# ledcube.net
KiCad netlist of a schematic drawn in EAGLE
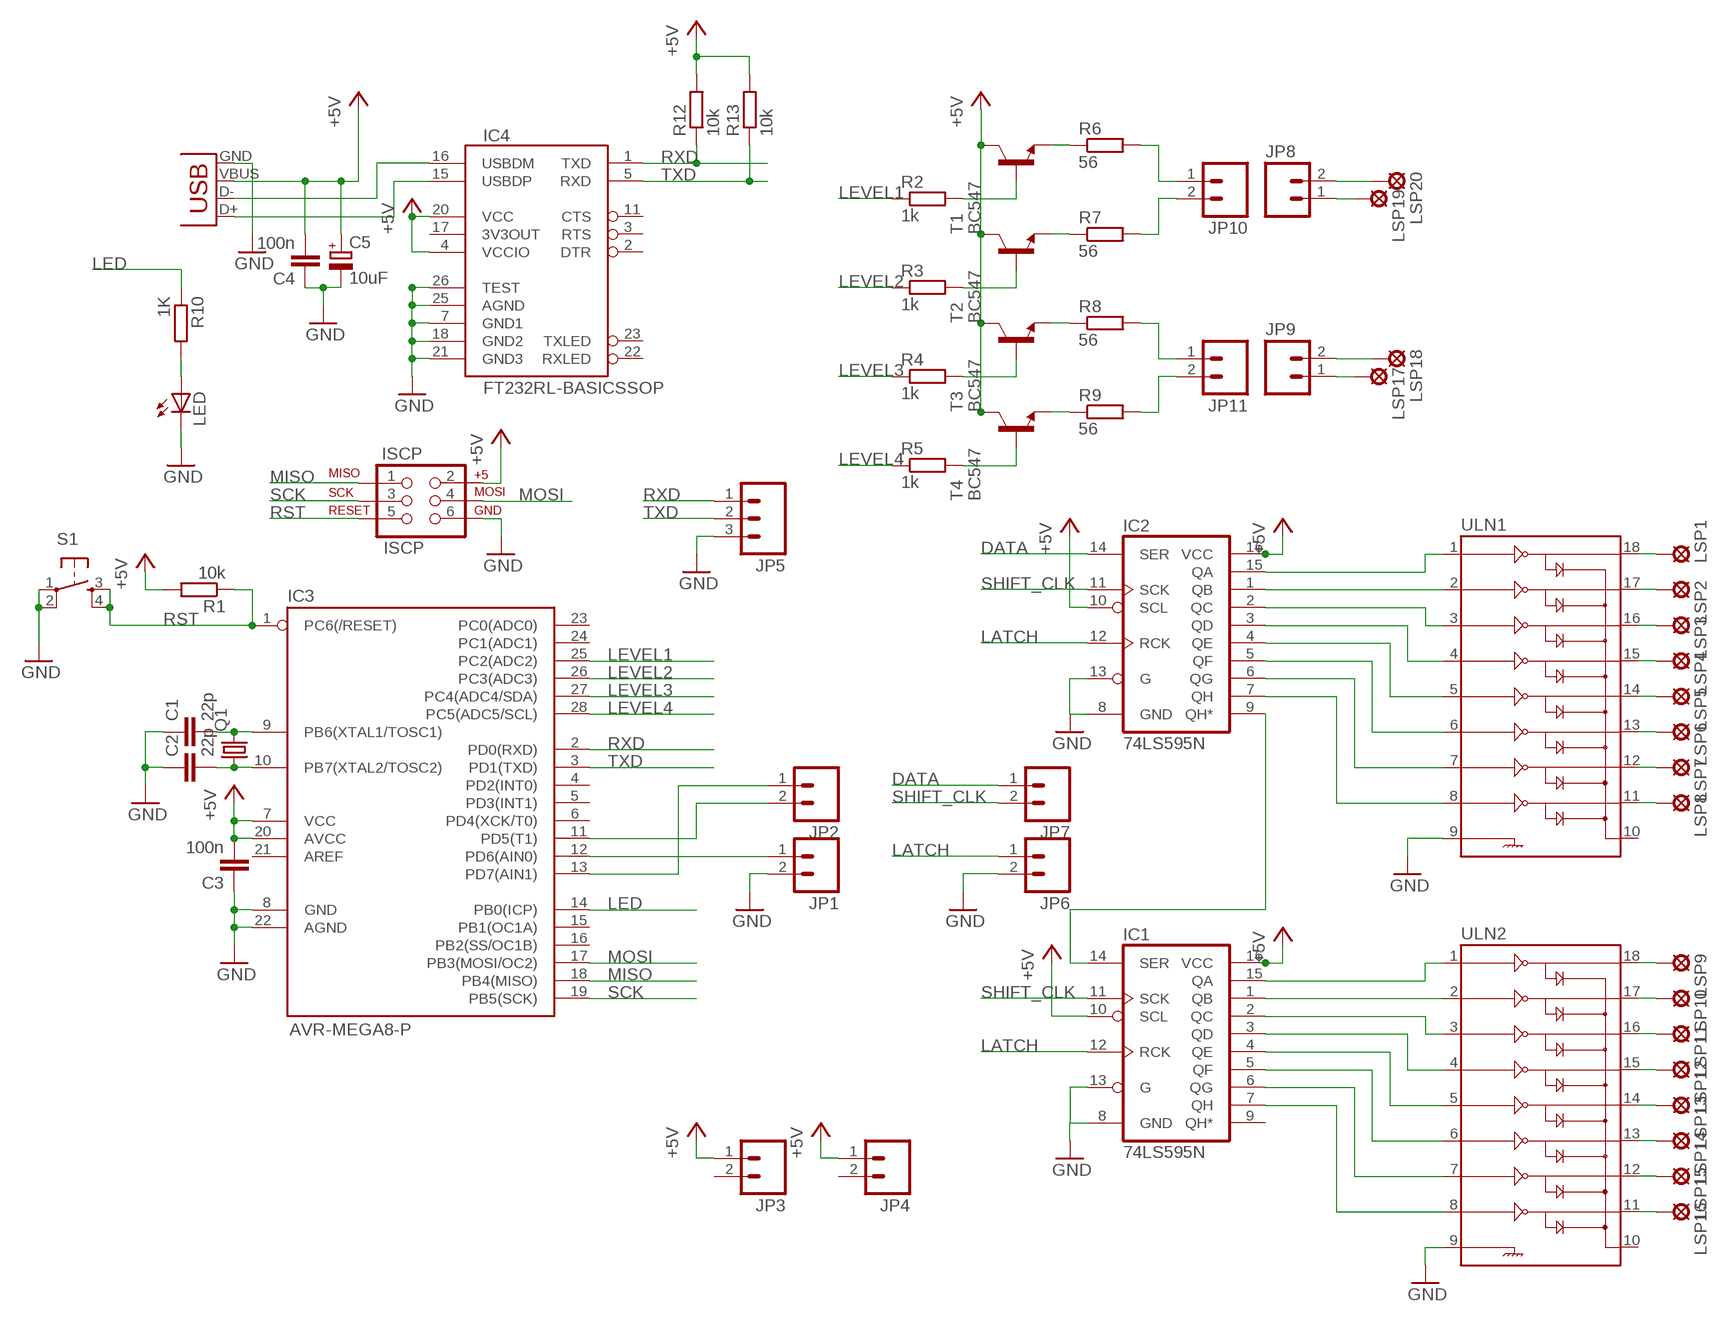
[diagram p0: schematic, sheet 1]

(export (version "E")
  (design (tool "Eeschema 10.0.6"))
  (components
    (comp (ref "C1")
      (value "22p")
      (footprint "eagle-import:C050-024X044")
      (libsource (lib "eagle-import") (part "C-EU050-024X044"))
    )
    (comp (ref "C2")
      (value "22p")
      (footprint "eagle-import:C050-024X044")
      (libsource (lib "eagle-import") (part "C-EU050-024X044"))
    )
    (comp (ref "C3")
      (value "100n")
      (footprint "eagle-import:C050-024X044")
      (libsource (lib "eagle-import") (part "C-EU050-024X044"))
    )
    (comp (ref "C4")
      (value "100n")
      (footprint "eagle-import:C050-024X044")
      (libsource (lib "eagle-import") (part "C-EU050-024X044"))
    )
    (comp (ref "C5")
      (value "10uF")
      (footprint "eagle-import:E2,5-6")
      (libsource (lib "eagle-import") (part "CPOL-EUE2.5-6"))
    )
    (comp (ref "IC1")
      (value "74LS595N")
      (footprint "eagle-import:DIL16")
      (libsource (lib "eagle-import") (part "74595NLS"))
    )
    (comp (ref "IC2")
      (value "74LS595N")
      (footprint "eagle-import:DIL16")
      (libsource (lib "eagle-import") (part "74595NLS"))
    )
    (comp (ref "IC3")
      (value "AVR-MEGA8-P")
      (footprint "eagle-import:DIL28-3")
      (libsource (lib "eagle-import") (part "AVR-MEGA8-P"))
    )
    (comp (ref "IC4")
      (value "FT232RL-BASICSSOP")
      (footprint "eagle-import:SSOP28DB")
      (libsource (lib "eagle-import") (part "FT232RL-BASICSSOP"))
    )
    (comp (ref "ISCP")
      (value "ISCP")
      (footprint "eagle-import:2X3-NS")
      (libsource (lib "eagle-import") (part "AVR_SPI_PRG_6NS"))
    )
    (comp (ref "JP1")
      (value "M02PTH3")
      (footprint "eagle-import:1X02_LONGPADS")
      (libsource (lib "eagle-import") (part "M02PTH3"))
    )
    (comp (ref "JP2")
      (value "M02PTH3")
      (footprint "eagle-import:1X02_LONGPADS")
      (libsource (lib "eagle-import") (part "M02PTH3"))
    )
    (comp (ref "JP3")
      (value "M02PTH3")
      (footprint "eagle-import:1X02_LONGPADS")
      (libsource (lib "eagle-import") (part "M02PTH3"))
    )
    (comp (ref "JP4")
      (value "M02PTH3")
      (footprint "eagle-import:1X02_LONGPADS")
      (libsource (lib "eagle-import") (part "M02PTH3"))
    )
    (comp (ref "JP5")
      (value "M03PTH")
      (footprint "eagle-import:1X03")
      (libsource (lib "eagle-import") (part "M03PTH"))
    )
    (comp (ref "JP6")
      (value "M02PTH3")
      (footprint "eagle-import:1X02_LONGPADS")
      (libsource (lib "eagle-import") (part "M02PTH3"))
    )
    (comp (ref "JP7")
      (value "M02PTH3")
      (footprint "eagle-import:1X02_LONGPADS")
      (libsource (lib "eagle-import") (part "M02PTH3"))
    )
    (comp (ref "JP8")
      (value "M02PTH3")
      (footprint "eagle-import:1X02_LONGPADS")
      (libsource (lib "eagle-import") (part "M02PTH3"))
    )
    (comp (ref "JP9")
      (value "M02PTH3")
      (footprint "eagle-import:1X02_LONGPADS")
      (libsource (lib "eagle-import") (part "M02PTH3"))
    )
    (comp (ref "JP10")
      (value "M02PTH3")
      (footprint "eagle-import:1X02_LONGPADS")
      (libsource (lib "eagle-import") (part "M02PTH3"))
    )
    (comp (ref "JP11")
      (value "M02PTH3")
      (footprint "eagle-import:1X02_LONGPADS")
      (libsource (lib "eagle-import") (part "M02PTH3"))
    )
    (comp (ref "LED")
      (value "LED3MM")
      (footprint "eagle-import:LED3MM")
      (libsource (lib "eagle-import") (part "LED3MM"))
    )
    (comp (ref "LSP1")
      (value "LSP10")
      (footprint "eagle-import:LSP10")
      (libsource (lib "eagle-import") (part "LSP10"))
    )
    (comp (ref "LSP2")
      (value "LSP10")
      (footprint "eagle-import:LSP10")
      (libsource (lib "eagle-import") (part "LSP10"))
    )
    (comp (ref "LSP3")
      (value "LSP10")
      (footprint "eagle-import:LSP10")
      (libsource (lib "eagle-import") (part "LSP10"))
    )
    (comp (ref "LSP4")
      (value "LSP10")
      (footprint "eagle-import:LSP10")
      (libsource (lib "eagle-import") (part "LSP10"))
    )
    (comp (ref "LSP5")
      (value "LSP10")
      (footprint "eagle-import:LSP10")
      (libsource (lib "eagle-import") (part "LSP10"))
    )
    (comp (ref "LSP6")
      (value "LSP10")
      (footprint "eagle-import:LSP10")
      (libsource (lib "eagle-import") (part "LSP10"))
    )
    (comp (ref "LSP7")
      (value "LSP10")
      (footprint "eagle-import:LSP10")
      (libsource (lib "eagle-import") (part "LSP10"))
    )
    (comp (ref "LSP8")
      (value "LSP10")
      (footprint "eagle-import:LSP10")
      (libsource (lib "eagle-import") (part "LSP10"))
    )
    (comp (ref "LSP9")
      (value "LSP10")
      (footprint "eagle-import:LSP10")
      (libsource (lib "eagle-import") (part "LSP10"))
    )
    (comp (ref "LSP10")
      (value "LSP10")
      (footprint "eagle-import:LSP10")
      (libsource (lib "eagle-import") (part "LSP10"))
    )
    (comp (ref "LSP11")
      (value "LSP10")
      (footprint "eagle-import:LSP10")
      (libsource (lib "eagle-import") (part "LSP10"))
    )
    (comp (ref "LSP12")
      (value "LSP10")
      (footprint "eagle-import:LSP10")
      (libsource (lib "eagle-import") (part "LSP10"))
    )
    (comp (ref "LSP13")
      (value "LSP10")
      (footprint "eagle-import:LSP10")
      (libsource (lib "eagle-import") (part "LSP10"))
    )
    (comp (ref "LSP14")
      (value "LSP10")
      (footprint "eagle-import:LSP10")
      (libsource (lib "eagle-import") (part "LSP10"))
    )
    (comp (ref "LSP15")
      (value "LSP10")
      (footprint "eagle-import:LSP10")
      (libsource (lib "eagle-import") (part "LSP10"))
    )
    (comp (ref "LSP16")
      (value "LSP10")
      (footprint "eagle-import:LSP10")
      (libsource (lib "eagle-import") (part "LSP10"))
    )
    (comp (ref "LSP17")
      (value "LSP10")
      (footprint "eagle-import:LSP10")
      (libsource (lib "eagle-import") (part "LSP10"))
    )
    (comp (ref "LSP18")
      (value "LSP10")
      (footprint "eagle-import:LSP10")
      (libsource (lib "eagle-import") (part "LSP10"))
    )
    (comp (ref "LSP19")
      (value "LSP10")
      (footprint "eagle-import:LSP10")
      (libsource (lib "eagle-import") (part "LSP10"))
    )
    (comp (ref "LSP20")
      (value "LSP10")
      (footprint "eagle-import:LSP10")
      (libsource (lib "eagle-import") (part "LSP10"))
    )
    (comp (ref "Q1")
      (value "CRYSTALHC49S")
      (footprint "eagle-import:HC49_S")
      (libsource (lib "eagle-import") (part "CRYSTALHC49S"))
    )
    (comp (ref "R1")
      (value "10k")
      (footprint "eagle-import:0204V")
      (libsource (lib "eagle-import") (part "R-EU_0204/2V"))
    )
    (comp (ref "R2")
      (value "1k")
      (footprint "eagle-import:0204V")
      (libsource (lib "eagle-import") (part "R-EU_0204/2V"))
    )
    (comp (ref "R3")
      (value "1k")
      (footprint "eagle-import:0204V")
      (libsource (lib "eagle-import") (part "R-EU_0204/2V"))
    )
    (comp (ref "R4")
      (value "1k")
      (footprint "eagle-import:0204V")
      (libsource (lib "eagle-import") (part "R-EU_0204/2V"))
    )
    (comp (ref "R5")
      (value "1k")
      (footprint "eagle-import:0204V")
      (libsource (lib "eagle-import") (part "R-EU_0204/2V"))
    )
    (comp (ref "R6")
      (value "56")
      (footprint "eagle-import:0204V")
      (libsource (lib "eagle-import") (part "R-EU_0204/2V"))
    )
    (comp (ref "R7")
      (value "56")
      (footprint "eagle-import:0204V")
      (libsource (lib "eagle-import") (part "R-EU_0204/2V"))
    )
    (comp (ref "R8")
      (value "56")
      (footprint "eagle-import:0204V")
      (libsource (lib "eagle-import") (part "R-EU_0204/2V"))
    )
    (comp (ref "R9")
      (value "56")
      (footprint "eagle-import:0204V")
      (libsource (lib "eagle-import") (part "R-EU_0204/2V"))
    )
    (comp (ref "R10")
      (value "1K")
      (footprint "eagle-import:0204V")
      (libsource (lib "eagle-import") (part "R-EU_0204/2V"))
    )
    (comp (ref "R12")
      (value "10k")
      (footprint "eagle-import:0204V")
      (libsource (lib "eagle-import") (part "R-EU_0204/2V"))
    )
    (comp (ref "R13")
      (value "10k")
      (footprint "eagle-import:0204V")
      (libsource (lib "eagle-import") (part "R-EU_0204/2V"))
    )
    (comp (ref "S1")
      (value "TAC_SWITCHPTH")
      (footprint "eagle-import:TACTILE-PTH")
      (libsource (lib "eagle-import") (part "TAC_SWITCHPTH"))
    )
    (comp (ref "T1")
      (value "BC547")
      (footprint "eagle-import:TO92")
      (libsource (lib "eagle-import") (part "BC547"))
    )
    (comp (ref "T2")
      (value "BC547")
      (footprint "eagle-import:TO92")
      (libsource (lib "eagle-import") (part "BC547"))
    )
    (comp (ref "T3")
      (value "BC547")
      (footprint "eagle-import:TO92")
      (libsource (lib "eagle-import") (part "BC547"))
    )
    (comp (ref "T4")
      (value "BC547")
      (footprint "eagle-import:TO92")
      (libsource (lib "eagle-import") (part "BC547"))
    )
    (comp (ref "ULN1")
      (value "ULN2803DIP")
      (footprint "eagle-import:DIL18")
      (libsource (lib "eagle-import") (part "ULN2803DIP"))
    )
    (comp (ref "ULN2")
      (value "ULN2803DIP")
      (footprint "eagle-import:DIL18")
      (libsource (lib "eagle-import") (part "ULN2803DIP"))
    )
    (comp (ref "X1")
      (value "USBSMD")
      (footprint "eagle-import:USB-MINIB")
      (libsource (lib "eagle-import") (part "USBSMD"))
    )
  )
  (nets
    (net (code "1") (name "+5V") (class "Default")
      (node (ref "C3") (pin "2") (pinfunction "2_2") (pintype "passive"))
      (node (ref "C4") (pin "2") (pinfunction "2_2") (pintype "passive"))
      (node (ref "C5") (pin "+") (pinfunction "+_+") (pintype "passive"))
      (node (ref "IC1") (pin "10") (pinfunction "SCL_10") (pintype "input"))
      (node (ref "IC1") (pin "16") (pinfunction "VCC_16") (pintype "power_in"))
      (node (ref "IC2") (pin "10") (pinfunction "SCL_10") (pintype "input"))
      (node (ref "IC2") (pin "16") (pinfunction "VCC_16") (pintype "power_in"))
      (node (ref "IC3") (pin "20") (pinfunction "AVCC_20") (pintype "bidirectional"))
      (node (ref "IC3") (pin "7") (pinfunction "VCC_7") (pintype "bidirectional"))
      (node (ref "IC4") (pin "20") (pinfunction "VCC_20") (pintype "power_in"))
      (node (ref "IC4") (pin "4") (pinfunction "VCCIO_4") (pintype "power_in"))
      (node (ref "ISCP") (pin "2") (pinfunction "2_2") (pintype "passive"))
      (node (ref "JP3") (pin "1") (pinfunction "1_1") (pintype "passive"))
      (node (ref "JP4") (pin "1") (pinfunction "1_1") (pintype "passive"))
      (node (ref "R1") (pin "2") (pinfunction "2_2") (pintype "passive"))
      (node (ref "R12") (pin "2") (pinfunction "2_2") (pintype "passive"))
      (node (ref "R13") (pin "2") (pinfunction "2_2") (pintype "passive"))
      (node (ref "T1") (pin "3") (pinfunction "C_3") (pintype "passive"))
      (node (ref "T2") (pin "3") (pinfunction "C_3") (pintype "passive"))
      (node (ref "T3") (pin "3") (pinfunction "C_3") (pintype "passive"))
      (node (ref "T4") (pin "3") (pinfunction "C_3") (pintype "passive"))
      (node (ref "X1") (pin "VBUS") (pinfunction "VBUS_VBUS") (pintype "bidirectional"))
    )
    (net (code "2") (name "/DATA") (class "Default")
      (node (ref "IC2") (pin "14") (pinfunction "SER_14") (pintype "input"))
      (node (ref "JP7") (pin "1") (pinfunction "1_1") (pintype "passive"))
    )
    (net (code "3") (name "/LATCH") (class "Default")
      (node (ref "IC1") (pin "12") (pinfunction "RCK_12") (pintype "input"))
      (node (ref "IC2") (pin "12") (pinfunction "RCK_12") (pintype "input"))
      (node (ref "JP6") (pin "1") (pinfunction "1_1") (pintype "passive"))
    )
    (net (code "4") (name "/LED") (class "Default")
      (node (ref "IC3") (pin "14") (pinfunction "PB0(ICP)_14") (pintype "bidirectional"))
      (node (ref "R10") (pin "1") (pinfunction "1_1") (pintype "passive"))
    )
    (net (code "5") (name "/LEVEL1") (class "Default")
      (node (ref "IC3") (pin "25") (pinfunction "PC2(ADC2)_25") (pintype "bidirectional"))
      (node (ref "R2") (pin "1") (pinfunction "1_1") (pintype "passive"))
    )
    (net (code "6") (name "/LEVEL2") (class "Default")
      (node (ref "IC3") (pin "26") (pinfunction "PC3(ADC3)_26") (pintype "bidirectional"))
      (node (ref "R3") (pin "1") (pinfunction "1_1") (pintype "passive"))
    )
    (net (code "7") (name "/LEVEL3") (class "Default")
      (node (ref "IC3") (pin "27") (pinfunction "PC4(ADC4/SDA)_27") (pintype "bidirectional"))
      (node (ref "R4") (pin "1") (pinfunction "1_1") (pintype "passive"))
    )
    (net (code "8") (name "/LEVEL4") (class "Default")
      (node (ref "IC3") (pin "28") (pinfunction "PC5(ADC5/SCL)_28") (pintype "bidirectional"))
      (node (ref "R5") (pin "1") (pinfunction "1_1") (pintype "passive"))
    )
    (net (code "9") (name "/MISO") (class "Default")
      (node (ref "IC3") (pin "18") (pinfunction "PB4(MISO)_18") (pintype "bidirectional"))
      (node (ref "ISCP") (pin "1") (pinfunction "1_1") (pintype "passive"))
    )
    (net (code "10") (name "/MOSI") (class "Default")
      (node (ref "IC3") (pin "17") (pinfunction "PB3(MOSI/OC2)_17") (pintype "bidirectional"))
      (node (ref "ISCP") (pin "4") (pinfunction "4_4") (pintype "passive"))
    )
    (net (code "11") (name "/RST") (class "Default")
      (node (ref "IC3") (pin "1") (pinfunction "PC6(/RESET)_1") (pintype "bidirectional"))
      (node (ref "ISCP") (pin "5") (pinfunction "5_5") (pintype "passive"))
      (node (ref "R1") (pin "1") (pinfunction "1_1") (pintype "passive"))
      (node (ref "S1") (pin "3") (pinfunction "3_3") (pintype "passive"))
      (node (ref "S1") (pin "4") (pinfunction "4_4") (pintype "passive"))
    )
    (net (code "12") (name "/RXD") (class "Default")
      (node (ref "IC3") (pin "2") (pinfunction "PD0(RXD)_2") (pintype "bidirectional"))
      (node (ref "IC4") (pin "1") (pinfunction "TXD_1") (pintype "output"))
      (node (ref "JP5") (pin "1") (pinfunction "1_1") (pintype "passive"))
      (node (ref "R12") (pin "1") (pinfunction "1_1") (pintype "passive"))
    )
    (net (code "13") (name "/SCK") (class "Default")
      (node (ref "IC3") (pin "19") (pinfunction "PB5(SCK)_19") (pintype "bidirectional"))
      (node (ref "ISCP") (pin "3") (pinfunction "3_3") (pintype "passive"))
    )
    (net (code "14") (name "/SHIFT_CLK") (class "Default")
      (node (ref "IC1") (pin "11") (pinfunction "SCK_11") (pintype "input"))
      (node (ref "IC2") (pin "11") (pinfunction "SCK_11") (pintype "input"))
      (node (ref "JP7") (pin "2") (pinfunction "2_2") (pintype "passive"))
    )
    (net (code "15") (name "/TXD") (class "Default")
      (node (ref "IC3") (pin "3") (pinfunction "PD1(TXD)_3") (pintype "bidirectional"))
      (node (ref "IC4") (pin "5") (pinfunction "RXD_5") (pintype "input"))
      (node (ref "JP5") (pin "2") (pinfunction "2_2") (pintype "passive"))
      (node (ref "R13") (pin "1") (pinfunction "1_1") (pintype "passive"))
    )
    (net (code "16") (name "GND") (class "Default")
      (node (ref "C1") (pin "1") (pinfunction "1_1") (pintype "passive"))
      (node (ref "C2") (pin "1") (pinfunction "1_1") (pintype "passive"))
      (node (ref "C3") (pin "1") (pinfunction "1_1") (pintype "passive"))
      (node (ref "C4") (pin "1") (pinfunction "1_1") (pintype "passive"))
      (node (ref "C5") (pin "-") (pinfunction "-_-") (pintype "passive"))
      (node (ref "IC1") (pin "13") (pinfunction "G_13") (pintype "input"))
      (node (ref "IC1") (pin "8") (pinfunction "GND_8") (pintype "power_in"))
      (node (ref "IC2") (pin "13") (pinfunction "G_13") (pintype "input"))
      (node (ref "IC2") (pin "8") (pinfunction "GND_8") (pintype "power_in"))
      (node (ref "IC3") (pin "22") (pinfunction "AGND_22") (pintype "bidirectional"))
      (node (ref "IC3") (pin "8") (pinfunction "GND_8") (pintype "bidirectional"))
      (node (ref "IC4") (pin "18") (pinfunction "GND2_18") (pintype "power_in"))
      (node (ref "IC4") (pin "21") (pinfunction "GND3_21") (pintype "power_in"))
      (node (ref "IC4") (pin "25") (pinfunction "AGND_25") (pintype "power_in"))
      (node (ref "IC4") (pin "26") (pinfunction "TEST_26") (pintype "input"))
      (node (ref "IC4") (pin "7") (pinfunction "GND1_7") (pintype "power_in"))
      (node (ref "ISCP") (pin "6") (pinfunction "6_6") (pintype "passive"))
      (node (ref "JP1") (pin "2") (pinfunction "2_2") (pintype "passive"))
      (node (ref "JP5") (pin "3") (pinfunction "3_3") (pintype "passive"))
      (node (ref "JP6") (pin "2") (pinfunction "2_2") (pintype "passive"))
      (node (ref "LED") (pin "K") (pinfunction "C_K") (pintype "passive"))
      (node (ref "S1") (pin "1") (pinfunction "1_1") (pintype "passive"))
      (node (ref "S1") (pin "2") (pinfunction "2_2") (pintype "passive"))
      (node (ref "ULN1") (pin "9") (pinfunction "9_9") (pintype "bidirectional"))
      (node (ref "ULN2") (pin "9") (pinfunction "9_9") (pintype "bidirectional"))
      (node (ref "X1") (pin "GND") (pinfunction "GND_GND") (pintype "bidirectional"))
    )
    (net (code "17") (name "Net-(IC1-QA)") (class "Default")
      (node (ref "IC1") (pin "15") (pinfunction "QA_15") (pintype "tri_state"))
      (node (ref "ULN2") (pin "1") (pinfunction "1_1") (pintype "bidirectional"))
    )
    (net (code "18") (name "Net-(IC1-QB)") (class "Default")
      (node (ref "IC1") (pin "1") (pinfunction "QB_1") (pintype "tri_state"))
      (node (ref "ULN2") (pin "2") (pinfunction "2_2") (pintype "bidirectional"))
    )
    (net (code "19") (name "Net-(IC1-QC)") (class "Default")
      (node (ref "IC1") (pin "2") (pinfunction "QC_2") (pintype "tri_state"))
      (node (ref "ULN2") (pin "3") (pinfunction "3_3") (pintype "bidirectional"))
    )
    (net (code "20") (name "Net-(IC1-QD)") (class "Default")
      (node (ref "IC1") (pin "3") (pinfunction "QD_3") (pintype "tri_state"))
      (node (ref "ULN2") (pin "4") (pinfunction "4_4") (pintype "bidirectional"))
    )
    (net (code "21") (name "Net-(IC1-QE)") (class "Default")
      (node (ref "IC1") (pin "4") (pinfunction "QE_4") (pintype "tri_state"))
      (node (ref "ULN2") (pin "5") (pinfunction "5_5") (pintype "bidirectional"))
    )
    (net (code "22") (name "Net-(IC1-QF)") (class "Default")
      (node (ref "IC1") (pin "5") (pinfunction "QF_5") (pintype "tri_state"))
      (node (ref "ULN2") (pin "6") (pinfunction "6_6") (pintype "bidirectional"))
    )
    (net (code "23") (name "Net-(IC1-QG)") (class "Default")
      (node (ref "IC1") (pin "6") (pinfunction "QG_6") (pintype "tri_state"))
      (node (ref "ULN2") (pin "7") (pinfunction "7_7") (pintype "bidirectional"))
    )
    (net (code "24") (name "Net-(IC1-QH)") (class "Default")
      (node (ref "IC1") (pin "7") (pinfunction "QH_7") (pintype "tri_state"))
      (node (ref "ULN2") (pin "8") (pinfunction "8_8") (pintype "bidirectional"))
    )
    (net (code "25") (name "Net-(IC1-SER)") (class "Default")
      (node (ref "IC1") (pin "14") (pinfunction "SER_14") (pintype "input"))
      (node (ref "IC2") (pin "9") (pinfunction "QH*_9") (pintype "tri_state"))
    )
    (net (code "26") (name "Net-(IC2-QA)") (class "Default")
      (node (ref "IC2") (pin "15") (pinfunction "QA_15") (pintype "tri_state"))
      (node (ref "ULN1") (pin "1") (pinfunction "1_1") (pintype "bidirectional"))
    )
    (net (code "27") (name "Net-(IC2-QB)") (class "Default")
      (node (ref "IC2") (pin "1") (pinfunction "QB_1") (pintype "tri_state"))
      (node (ref "ULN1") (pin "2") (pinfunction "2_2") (pintype "bidirectional"))
    )
    (net (code "28") (name "Net-(IC2-QC)") (class "Default")
      (node (ref "IC2") (pin "2") (pinfunction "QC_2") (pintype "tri_state"))
      (node (ref "ULN1") (pin "3") (pinfunction "3_3") (pintype "bidirectional"))
    )
    (net (code "29") (name "Net-(IC2-QD)") (class "Default")
      (node (ref "IC2") (pin "3") (pinfunction "QD_3") (pintype "tri_state"))
      (node (ref "ULN1") (pin "4") (pinfunction "4_4") (pintype "bidirectional"))
    )
    (net (code "30") (name "Net-(IC2-QE)") (class "Default")
      (node (ref "IC2") (pin "4") (pinfunction "QE_4") (pintype "tri_state"))
      (node (ref "ULN1") (pin "5") (pinfunction "5_5") (pintype "bidirectional"))
    )
    (net (code "31") (name "Net-(IC2-QF)") (class "Default")
      (node (ref "IC2") (pin "5") (pinfunction "QF_5") (pintype "tri_state"))
      (node (ref "ULN1") (pin "6") (pinfunction "6_6") (pintype "bidirectional"))
    )
    (net (code "32") (name "Net-(IC2-QG)") (class "Default")
      (node (ref "IC2") (pin "6") (pinfunction "QG_6") (pintype "tri_state"))
      (node (ref "ULN1") (pin "7") (pinfunction "7_7") (pintype "bidirectional"))
    )
    (net (code "33") (name "Net-(IC2-QH)") (class "Default")
      (node (ref "IC2") (pin "7") (pinfunction "QH_7") (pintype "tri_state"))
      (node (ref "ULN1") (pin "8") (pinfunction "8_8") (pintype "bidirectional"))
    )
    (net (code "34") (name "Net-(IC3-PB6(XTAL1{slash}TOSC1))") (class "Default")
      (node (ref "C1") (pin "2") (pinfunction "2_2") (pintype "passive"))
      (node (ref "IC3") (pin "9") (pinfunction "PB6(XTAL1/TOSC1)_9") (pintype "bidirectional"))
      (node (ref "Q1") (pin "2") (pinfunction "2_2") (pintype "passive"))
    )
    (net (code "35") (name "Net-(IC3-PB7(XTAL2{slash}TOSC2))") (class "Default")
      (node (ref "C2") (pin "2") (pinfunction "2_2") (pintype "passive"))
      (node (ref "IC3") (pin "10") (pinfunction "PB7(XTAL2/TOSC2)_10") (pintype "bidirectional"))
      (node (ref "Q1") (pin "1") (pinfunction "1_1") (pintype "passive"))
    )
    (net (code "36") (name "Net-(IC3-PD5(T1))") (class "Default")
      (node (ref "IC3") (pin "11") (pinfunction "PD5(T1)_11") (pintype "bidirectional"))
      (node (ref "JP2") (pin "2") (pinfunction "2_2") (pintype "passive"))
    )
    (net (code "37") (name "Net-(IC3-PD6(AIN0))") (class "Default")
      (node (ref "IC3") (pin "12") (pinfunction "PD6(AIN0)_12") (pintype "bidirectional"))
      (node (ref "JP1") (pin "1") (pinfunction "1_1") (pintype "passive"))
    )
    (net (code "38") (name "Net-(IC3-PD7(AIN1))") (class "Default")
      (node (ref "IC3") (pin "13") (pinfunction "PD7(AIN1)_13") (pintype "bidirectional"))
      (node (ref "JP2") (pin "1") (pinfunction "1_1") (pintype "passive"))
    )
    (net (code "39") (name "Net-(IC4-USBDM)") (class "Default")
      (node (ref "IC4") (pin "16") (pinfunction "USBDM_16") (pintype "bidirectional"))
      (node (ref "X1") (pin "D-") (pinfunction "D-_D-") (pintype "bidirectional"))
    )
    (net (code "40") (name "Net-(IC4-USBDP)") (class "Default")
      (node (ref "IC4") (pin "15") (pinfunction "USBDP_15") (pintype "bidirectional"))
      (node (ref "X1") (pin "D+") (pinfunction "D+_D+") (pintype "bidirectional"))
    )
    (net (code "41") (name "Net-(JP8-Pad1)") (class "Default")
      (node (ref "JP8") (pin "1") (pinfunction "1_1") (pintype "passive"))
      (node (ref "LSP19") (pin "MP") (pinfunction "MP_MP") (pintype "passive"))
    )
    (net (code "42") (name "Net-(JP8-Pad2)") (class "Default")
      (node (ref "JP8") (pin "2") (pinfunction "2_2") (pintype "passive"))
      (node (ref "LSP20") (pin "MP") (pinfunction "MP_MP") (pintype "passive"))
    )
    (net (code "43") (name "Net-(JP9-Pad1)") (class "Default")
      (node (ref "JP9") (pin "1") (pinfunction "1_1") (pintype "passive"))
      (node (ref "LSP17") (pin "MP") (pinfunction "MP_MP") (pintype "passive"))
    )
    (net (code "44") (name "Net-(JP9-Pad2)") (class "Default")
      (node (ref "JP9") (pin "2") (pinfunction "2_2") (pintype "passive"))
      (node (ref "LSP18") (pin "MP") (pinfunction "MP_MP") (pintype "passive"))
    )
    (net (code "45") (name "Net-(JP10-Pad1)") (class "Default")
      (node (ref "JP10") (pin "1") (pinfunction "1_1") (pintype "passive"))
      (node (ref "R6") (pin "2") (pinfunction "2_2") (pintype "passive"))
    )
    (net (code "46") (name "Net-(JP10-Pad2)") (class "Default")
      (node (ref "JP10") (pin "2") (pinfunction "2_2") (pintype "passive"))
      (node (ref "R7") (pin "2") (pinfunction "2_2") (pintype "passive"))
    )
    (net (code "47") (name "Net-(JP11-Pad1)") (class "Default")
      (node (ref "JP11") (pin "1") (pinfunction "1_1") (pintype "passive"))
      (node (ref "R8") (pin "2") (pinfunction "2_2") (pintype "passive"))
    )
    (net (code "48") (name "Net-(JP11-Pad2)") (class "Default")
      (node (ref "JP11") (pin "2") (pinfunction "2_2") (pintype "passive"))
      (node (ref "R9") (pin "2") (pinfunction "2_2") (pintype "passive"))
    )
    (net (code "49") (name "Net-(LED-PadA)") (class "Default")
      (node (ref "LED") (pin "A") (pinfunction "A_A") (pintype "passive"))
      (node (ref "R10") (pin "2") (pinfunction "2_2") (pintype "passive"))
    )
    (net (code "50") (name "Net-(LSP1-PadMP)") (class "Default")
      (node (ref "LSP1") (pin "MP") (pinfunction "MP_MP") (pintype "passive"))
      (node (ref "ULN1") (pin "18") (pinfunction "18_18") (pintype "bidirectional"))
    )
    (net (code "51") (name "Net-(LSP2-PadMP)") (class "Default")
      (node (ref "LSP2") (pin "MP") (pinfunction "MP_MP") (pintype "passive"))
      (node (ref "ULN1") (pin "17") (pinfunction "17_17") (pintype "bidirectional"))
    )
    (net (code "52") (name "Net-(LSP3-PadMP)") (class "Default")
      (node (ref "LSP3") (pin "MP") (pinfunction "MP_MP") (pintype "passive"))
      (node (ref "ULN1") (pin "16") (pinfunction "16_16") (pintype "bidirectional"))
    )
    (net (code "53") (name "Net-(LSP4-PadMP)") (class "Default")
      (node (ref "LSP4") (pin "MP") (pinfunction "MP_MP") (pintype "passive"))
      (node (ref "ULN1") (pin "15") (pinfunction "15_15") (pintype "bidirectional"))
    )
    (net (code "54") (name "Net-(LSP5-PadMP)") (class "Default")
      (node (ref "LSP5") (pin "MP") (pinfunction "MP_MP") (pintype "passive"))
      (node (ref "ULN1") (pin "14") (pinfunction "14_14") (pintype "bidirectional"))
    )
    (net (code "55") (name "Net-(LSP6-PadMP)") (class "Default")
      (node (ref "LSP6") (pin "MP") (pinfunction "MP_MP") (pintype "passive"))
      (node (ref "ULN1") (pin "13") (pinfunction "13_13") (pintype "bidirectional"))
    )
    (net (code "56") (name "Net-(LSP7-PadMP)") (class "Default")
      (node (ref "LSP7") (pin "MP") (pinfunction "MP_MP") (pintype "passive"))
      (node (ref "ULN1") (pin "12") (pinfunction "12_12") (pintype "bidirectional"))
    )
    (net (code "57") (name "Net-(LSP8-PadMP)") (class "Default")
      (node (ref "LSP8") (pin "MP") (pinfunction "MP_MP") (pintype "passive"))
      (node (ref "ULN1") (pin "11") (pinfunction "11_11") (pintype "bidirectional"))
    )
    (net (code "58") (name "Net-(LSP9-PadMP)") (class "Default")
      (node (ref "LSP9") (pin "MP") (pinfunction "MP_MP") (pintype "passive"))
      (node (ref "ULN2") (pin "18") (pinfunction "18_18") (pintype "bidirectional"))
    )
    (net (code "59") (name "Net-(LSP10-PadMP)") (class "Default")
      (node (ref "LSP10") (pin "MP") (pinfunction "MP_MP") (pintype "passive"))
      (node (ref "ULN2") (pin "17") (pinfunction "17_17") (pintype "bidirectional"))
    )
    (net (code "60") (name "Net-(LSP11-PadMP)") (class "Default")
      (node (ref "LSP11") (pin "MP") (pinfunction "MP_MP") (pintype "passive"))
      (node (ref "ULN2") (pin "16") (pinfunction "16_16") (pintype "bidirectional"))
    )
    (net (code "61") (name "Net-(LSP12-PadMP)") (class "Default")
      (node (ref "LSP12") (pin "MP") (pinfunction "MP_MP") (pintype "passive"))
      (node (ref "ULN2") (pin "15") (pinfunction "15_15") (pintype "bidirectional"))
    )
    (net (code "62") (name "Net-(LSP13-PadMP)") (class "Default")
      (node (ref "LSP13") (pin "MP") (pinfunction "MP_MP") (pintype "passive"))
      (node (ref "ULN2") (pin "14") (pinfunction "14_14") (pintype "bidirectional"))
    )
    (net (code "63") (name "Net-(LSP14-PadMP)") (class "Default")
      (node (ref "LSP14") (pin "MP") (pinfunction "MP_MP") (pintype "passive"))
      (node (ref "ULN2") (pin "13") (pinfunction "13_13") (pintype "bidirectional"))
    )
    (net (code "64") (name "Net-(LSP15-PadMP)") (class "Default")
      (node (ref "LSP15") (pin "MP") (pinfunction "MP_MP") (pintype "passive"))
      (node (ref "ULN2") (pin "12") (pinfunction "12_12") (pintype "bidirectional"))
    )
    (net (code "65") (name "Net-(LSP16-PadMP)") (class "Default")
      (node (ref "LSP16") (pin "MP") (pinfunction "MP_MP") (pintype "passive"))
      (node (ref "ULN2") (pin "11") (pinfunction "11_11") (pintype "bidirectional"))
    )
    (net (code "66") (name "Net-(T1-B)") (class "Default")
      (node (ref "R2") (pin "2") (pinfunction "2_2") (pintype "passive"))
      (node (ref "T1") (pin "2") (pinfunction "B_2") (pintype "passive"))
    )
    (net (code "67") (name "Net-(T1-E)") (class "Default")
      (node (ref "R6") (pin "1") (pinfunction "1_1") (pintype "passive"))
      (node (ref "T1") (pin "1") (pinfunction "E_1") (pintype "passive"))
    )
    (net (code "68") (name "Net-(T2-B)") (class "Default")
      (node (ref "R3") (pin "2") (pinfunction "2_2") (pintype "passive"))
      (node (ref "T2") (pin "2") (pinfunction "B_2") (pintype "passive"))
    )
    (net (code "69") (name "Net-(T2-E)") (class "Default")
      (node (ref "R7") (pin "1") (pinfunction "1_1") (pintype "passive"))
      (node (ref "T2") (pin "1") (pinfunction "E_1") (pintype "passive"))
    )
    (net (code "70") (name "Net-(T3-B)") (class "Default")
      (node (ref "R4") (pin "2") (pinfunction "2_2") (pintype "passive"))
      (node (ref "T3") (pin "2") (pinfunction "B_2") (pintype "passive"))
    )
    (net (code "71") (name "Net-(T3-E)") (class "Default")
      (node (ref "R8") (pin "1") (pinfunction "1_1") (pintype "passive"))
      (node (ref "T3") (pin "1") (pinfunction "E_1") (pintype "passive"))
    )
    (net (code "72") (name "Net-(T4-B)") (class "Default")
      (node (ref "R5") (pin "2") (pinfunction "2_2") (pintype "passive"))
      (node (ref "T4") (pin "2") (pinfunction "B_2") (pintype "passive"))
    )
    (net (code "73") (name "Net-(T4-E)") (class "Default")
      (node (ref "R9") (pin "1") (pinfunction "1_1") (pintype "passive"))
      (node (ref "T4") (pin "1") (pinfunction "E_1") (pintype "passive"))
    )
    (net (code "74") (name "unconnected-(IC1-QH*-Pad9)") (class "Default")
      (node (ref "IC1") (pin "9") (pinfunction "QH*_9") (pintype "tri_state"))
    )
    (net (code "75") (name "unconnected-(IC3-AREF-Pad21)") (class "Default")
      (node (ref "IC3") (pin "21") (pinfunction "AREF_21") (pintype "bidirectional"))
    )
    (net (code "76") (name "unconnected-(IC3-PB1(OC1A)-Pad15)") (class "Default")
      (node (ref "IC3") (pin "15") (pinfunction "PB1(OC1A)_15") (pintype "bidirectional"))
    )
    (net (code "77") (name "unconnected-(IC3-PB2(SS{slash}OC1B)-Pad16)") (class "Default")
      (node (ref "IC3") (pin "16") (pinfunction "PB2(SS/OC1B)_16") (pintype "bidirectional"))
    )
    (net (code "78") (name "unconnected-(IC3-PC0(ADC0)-Pad23)") (class "Default")
      (node (ref "IC3") (pin "23") (pinfunction "PC0(ADC0)_23") (pintype "bidirectional"))
    )
    (net (code "79") (name "unconnected-(IC3-PC1(ADC1)-Pad24)") (class "Default")
      (node (ref "IC3") (pin "24") (pinfunction "PC1(ADC1)_24") (pintype "bidirectional"))
    )
    (net (code "80") (name "unconnected-(IC3-PD2(INT0)-Pad4)") (class "Default")
      (node (ref "IC3") (pin "4") (pinfunction "PD2(INT0)_4") (pintype "bidirectional"))
    )
    (net (code "81") (name "unconnected-(IC3-PD3(INT1)-Pad5)") (class "Default")
      (node (ref "IC3") (pin "5") (pinfunction "PD3(INT1)_5") (pintype "bidirectional"))
    )
    (net (code "82") (name "unconnected-(IC3-PD4(XCK{slash}T0)-Pad6)") (class "Default")
      (node (ref "IC3") (pin "6") (pinfunction "PD4(XCK/T0)_6") (pintype "bidirectional"))
    )
    (net (code "83") (name "unconnected-(IC4-3V3OUT-Pad17)") (class "Default")
      (node (ref "IC4") (pin "17") (pinfunction "3V3OUT_17") (pintype "output"))
    )
    (net (code "84") (name "unconnected-(IC4-CTS-Pad11)") (class "Default")
      (node (ref "IC4") (pin "11") (pinfunction "CTS_11") (pintype "bidirectional"))
    )
    (net (code "85") (name "unconnected-(IC4-DTR-Pad2)") (class "Default")
      (node (ref "IC4") (pin "2") (pinfunction "DTR_2") (pintype "bidirectional"))
    )
    (net (code "86") (name "unconnected-(IC4-RTS-Pad3)") (class "Default")
      (node (ref "IC4") (pin "3") (pinfunction "RTS_3") (pintype "bidirectional"))
    )
    (net (code "87") (name "unconnected-(IC4-RXLED-Pad22)") (class "Default")
      (node (ref "IC4") (pin "22") (pinfunction "RXLED_22") (pintype "bidirectional"))
    )
    (net (code "88") (name "unconnected-(IC4-TXLED-Pad23)") (class "Default")
      (node (ref "IC4") (pin "23") (pinfunction "TXLED_23") (pintype "bidirectional"))
    )
    (net (code "89") (name "unconnected-(JP3-Pad2)") (class "Default")
      (node (ref "JP3") (pin "2") (pinfunction "2_2") (pintype "passive"))
    )
    (net (code "90") (name "unconnected-(JP4-Pad2)") (class "Default")
      (node (ref "JP4") (pin "2") (pinfunction "2_2") (pintype "passive"))
    )
    (net (code "91") (name "unconnected-(ULN1-Pad10)") (class "Default")
      (node (ref "ULN1") (pin "10") (pinfunction "10_10") (pintype "bidirectional"))
    )
    (net (code "92") (name "unconnected-(ULN2-Pad10)") (class "Default")
      (node (ref "ULN2") (pin "10") (pinfunction "10_10") (pintype "bidirectional"))
    )
  )
)
